# inputsheild_7.net
KiCad netlist of a schematic drawn in EAGLE
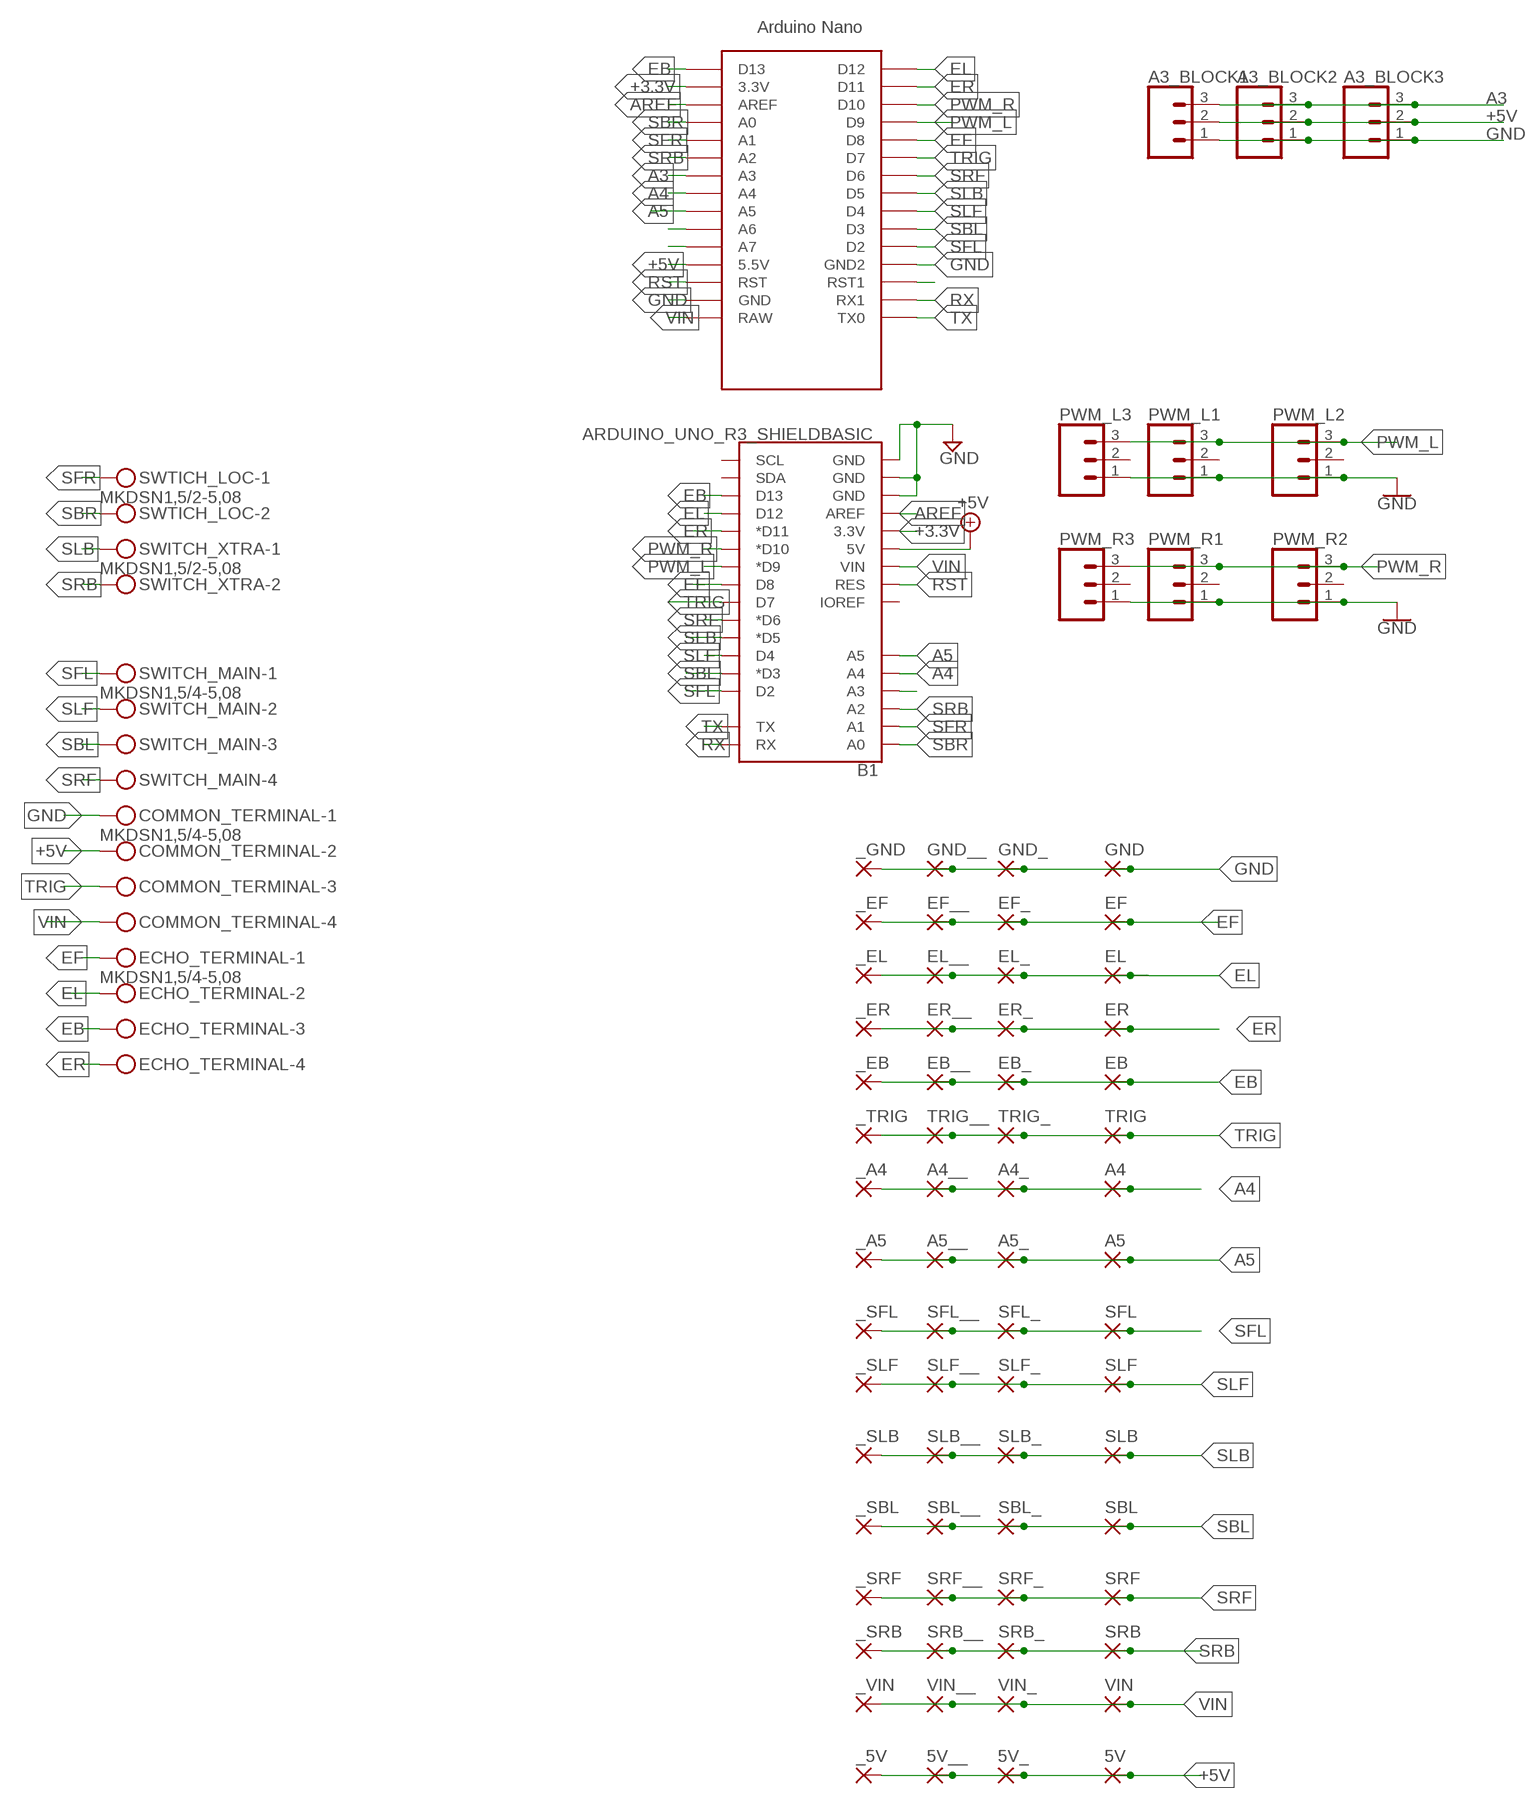
[diagram p0: schematic, sheet 1]

(export (version "E")
  (design (tool "Eeschema 10.0.6"))
  (components
    (comp (ref "5V")
      (value "SMD5")
      (footprint "eagle-import:SMD2,54-5,08")
      (libsource (lib "eagle-import") (part "SMD5"))
    )
    (comp (ref "5V_")
      (value "SMD5")
      (footprint "eagle-import:SMD2,54-5,08")
      (libsource (lib "eagle-import") (part "SMD5"))
    )
    (comp (ref "5V__")
      (value "SMD5")
      (footprint "eagle-import:SMD2,54-5,08")
      (libsource (lib "eagle-import") (part "SMD5"))
    )
    (comp (ref "A3_BLOCK1")
      (value "CONN_03")
      (footprint "eagle-import:1X03")
      (libsource (lib "eagle-import") (part "CONN_03"))
    )
    (comp (ref "A3_BLOCK2")
      (value "CONN_03")
      (footprint "eagle-import:1X03")
      (libsource (lib "eagle-import") (part "CONN_03"))
    )
    (comp (ref "A3_BLOCK3")
      (value "CONN_03")
      (footprint "eagle-import:1X03")
      (libsource (lib "eagle-import") (part "CONN_03"))
    )
    (comp (ref "A4")
      (value "SMD5")
      (footprint "eagle-import:SMD2,54-5,08")
      (libsource (lib "eagle-import") (part "SMD5"))
    )
    (comp (ref "A4_")
      (value "SMD5")
      (footprint "eagle-import:SMD2,54-5,08")
      (libsource (lib "eagle-import") (part "SMD5"))
    )
    (comp (ref "A4__")
      (value "SMD5")
      (footprint "eagle-import:SMD2,54-5,08")
      (libsource (lib "eagle-import") (part "SMD5"))
    )
    (comp (ref "A5")
      (value "SMD5")
      (footprint "eagle-import:SMD2,54-5,08")
      (libsource (lib "eagle-import") (part "SMD5"))
    )
    (comp (ref "A5_")
      (value "SMD5")
      (footprint "eagle-import:SMD2,54-5,08")
      (libsource (lib "eagle-import") (part "SMD5"))
    )
    (comp (ref "A5__")
      (value "SMD5")
      (footprint "eagle-import:SMD2,54-5,08")
      (libsource (lib "eagle-import") (part "SMD5"))
    )
    (comp (ref "B1")
      (value "ARDUINO_UNO_R3_SHIELDBASIC")
      (footprint "eagle-import:UNO_R3_SHIELD")
      (libsource (lib "eagle-import") (part "ARDUINO_UNO_R3_SHIELDBASIC"))
    )
    (comp (ref "COMMON_TERMINAL")
      (value "MKDSN1,5/4-5,08")
      (footprint "eagle-import:MKDSN1,5_4-5,08")
      (libsource (lib "eagle-import") (part "MKDSN1,5/4-5,08"))
    )
    (comp (ref "EB")
      (value "SMD5")
      (footprint "eagle-import:SMD2,54-5,08")
      (libsource (lib "eagle-import") (part "SMD5"))
    )
    (comp (ref "EB_")
      (value "SMD5")
      (footprint "eagle-import:SMD2,54-5,08")
      (libsource (lib "eagle-import") (part "SMD5"))
    )
    (comp (ref "EB__")
      (value "SMD5")
      (footprint "eagle-import:SMD2,54-5,08")
      (libsource (lib "eagle-import") (part "SMD5"))
    )
    (comp (ref "ECHO_TERMINAL")
      (value "MKDSN1,5/4-5,08")
      (footprint "eagle-import:MKDSN1,5_4-5,08")
      (libsource (lib "eagle-import") (part "MKDSN1,5/4-5,08"))
    )
    (comp (ref "EF")
      (value "SMD5")
      (footprint "eagle-import:SMD2,54-5,08")
      (libsource (lib "eagle-import") (part "SMD5"))
    )
    (comp (ref "EF_")
      (value "SMD5")
      (footprint "eagle-import:SMD2,54-5,08")
      (libsource (lib "eagle-import") (part "SMD5"))
    )
    (comp (ref "EF__")
      (value "SMD5")
      (footprint "eagle-import:SMD2,54-5,08")
      (libsource (lib "eagle-import") (part "SMD5"))
    )
    (comp (ref "EL")
      (value "SMD5")
      (footprint "eagle-import:SMD2,54-5,08")
      (libsource (lib "eagle-import") (part "SMD5"))
    )
    (comp (ref "EL_")
      (value "SMD5")
      (footprint "eagle-import:SMD2,54-5,08")
      (libsource (lib "eagle-import") (part "SMD5"))
    )
    (comp (ref "EL__")
      (value "SMD5")
      (footprint "eagle-import:SMD2,54-5,08")
      (libsource (lib "eagle-import") (part "SMD5"))
    )
    (comp (ref "ER")
      (value "SMD5")
      (footprint "eagle-import:SMD2,54-5,08")
      (libsource (lib "eagle-import") (part "SMD5"))
    )
    (comp (ref "ER_")
      (value "SMD5")
      (footprint "eagle-import:SMD2,54-5,08")
      (libsource (lib "eagle-import") (part "SMD5"))
    )
    (comp (ref "ER__")
      (value "SMD5")
      (footprint "eagle-import:SMD2,54-5,08")
      (libsource (lib "eagle-import") (part "SMD5"))
    )
    (comp (ref "GND")
      (value "SMD5")
      (footprint "eagle-import:SMD2,54-5,08")
      (libsource (lib "eagle-import") (part "SMD5"))
    )
    (comp (ref "GND_")
      (value "SMD5")
      (footprint "eagle-import:SMD2,54-5,08")
      (libsource (lib "eagle-import") (part "SMD5"))
    )
    (comp (ref "GND__")
      (value "SMD5")
      (footprint "eagle-import:SMD2,54-5,08")
      (libsource (lib "eagle-import") (part "SMD5"))
    )
    (comp (ref "PWM_L1")
      (value "CONN_03")
      (footprint "eagle-import:1X03")
      (libsource (lib "eagle-import") (part "CONN_03"))
    )
    (comp (ref "PWM_L2")
      (value "CONN_03")
      (footprint "eagle-import:1X03")
      (libsource (lib "eagle-import") (part "CONN_03"))
    )
    (comp (ref "PWM_L3")
      (value "CONN_03")
      (footprint "eagle-import:1X03")
      (libsource (lib "eagle-import") (part "CONN_03"))
    )
    (comp (ref "PWM_R1")
      (value "CONN_03")
      (footprint "eagle-import:1X03")
      (libsource (lib "eagle-import") (part "CONN_03"))
    )
    (comp (ref "PWM_R2")
      (value "CONN_03")
      (footprint "eagle-import:1X03")
      (libsource (lib "eagle-import") (part "CONN_03"))
    )
    (comp (ref "PWM_R3")
      (value "CONN_03")
      (footprint "eagle-import:1X03")
      (libsource (lib "eagle-import") (part "CONN_03"))
    )
    (comp (ref "SBL")
      (value "SMD5")
      (footprint "eagle-import:SMD2,54-5,08")
      (libsource (lib "eagle-import") (part "SMD5"))
    )
    (comp (ref "SBL_")
      (value "SMD5")
      (footprint "eagle-import:SMD2,54-5,08")
      (libsource (lib "eagle-import") (part "SMD5"))
    )
    (comp (ref "SBL__")
      (value "SMD5")
      (footprint "eagle-import:SMD2,54-5,08")
      (libsource (lib "eagle-import") (part "SMD5"))
    )
    (comp (ref "SFL")
      (value "SMD5")
      (footprint "eagle-import:SMD2,54-5,08")
      (libsource (lib "eagle-import") (part "SMD5"))
    )
    (comp (ref "SFL_")
      (value "SMD5")
      (footprint "eagle-import:SMD2,54-5,08")
      (libsource (lib "eagle-import") (part "SMD5"))
    )
    (comp (ref "SFL__")
      (value "SMD5")
      (footprint "eagle-import:SMD2,54-5,08")
      (libsource (lib "eagle-import") (part "SMD5"))
    )
    (comp (ref "SLB")
      (value "SMD5")
      (footprint "eagle-import:SMD2,54-5,08")
      (libsource (lib "eagle-import") (part "SMD5"))
    )
    (comp (ref "SLB_")
      (value "SMD5")
      (footprint "eagle-import:SMD2,54-5,08")
      (libsource (lib "eagle-import") (part "SMD5"))
    )
    (comp (ref "SLB__")
      (value "SMD5")
      (footprint "eagle-import:SMD2,54-5,08")
      (libsource (lib "eagle-import") (part "SMD5"))
    )
    (comp (ref "SLF")
      (value "SMD5")
      (footprint "eagle-import:SMD2,54-5,08")
      (libsource (lib "eagle-import") (part "SMD5"))
    )
    (comp (ref "SLF_")
      (value "SMD5")
      (footprint "eagle-import:SMD2,54-5,08")
      (libsource (lib "eagle-import") (part "SMD5"))
    )
    (comp (ref "SLF__")
      (value "SMD5")
      (footprint "eagle-import:SMD2,54-5,08")
      (libsource (lib "eagle-import") (part "SMD5"))
    )
    (comp (ref "SRB")
      (value "SMD5")
      (footprint "eagle-import:SMD2,54-5,08")
      (libsource (lib "eagle-import") (part "SMD5"))
    )
    (comp (ref "SRB_")
      (value "SMD5")
      (footprint "eagle-import:SMD2,54-5,08")
      (libsource (lib "eagle-import") (part "SMD5"))
    )
    (comp (ref "SRB__")
      (value "SMD5")
      (footprint "eagle-import:SMD2,54-5,08")
      (libsource (lib "eagle-import") (part "SMD5"))
    )
    (comp (ref "SRF")
      (value "SMD5")
      (footprint "eagle-import:SMD2,54-5,08")
      (libsource (lib "eagle-import") (part "SMD5"))
    )
    (comp (ref "SRF_")
      (value "SMD5")
      (footprint "eagle-import:SMD2,54-5,08")
      (libsource (lib "eagle-import") (part "SMD5"))
    )
    (comp (ref "SRF__")
      (value "SMD5")
      (footprint "eagle-import:SMD2,54-5,08")
      (libsource (lib "eagle-import") (part "SMD5"))
    )
    (comp (ref "SWITCH_MAIN")
      (value "MKDSN1,5/4-5,08")
      (footprint "eagle-import:MKDSN1,5_4-5,08")
      (libsource (lib "eagle-import") (part "MKDSN1,5/4-5,08"))
    )
    (comp (ref "SWITCH_XTRA")
      (value "MKDSN1,5/2-5,08")
      (footprint "eagle-import:MKDSN1,5_2-5,08")
      (libsource (lib "eagle-import") (part "MKDSN1,5/2-5,08"))
    )
    (comp (ref "SWTICH_LOC")
      (value "MKDSN1,5/2-5,08")
      (footprint "eagle-import:MKDSN1,5_2-5,08")
      (libsource (lib "eagle-import") (part "MKDSN1,5/2-5,08"))
    )
    (comp (ref "TRIG")
      (value "SMD5")
      (footprint "eagle-import:SMD2,54-5,08")
      (libsource (lib "eagle-import") (part "SMD5"))
    )
    (comp (ref "TRIG_")
      (value "SMD5")
      (footprint "eagle-import:SMD2,54-5,08")
      (libsource (lib "eagle-import") (part "SMD5"))
    )
    (comp (ref "TRIG__")
      (value "SMD5")
      (footprint "eagle-import:SMD2,54-5,08")
      (libsource (lib "eagle-import") (part "SMD5"))
    )
    (comp (ref "U$1")
      (value "NANO")
      (footprint "eagle-import:NANO")
      (libsource (lib "eagle-import") (part "NANO"))
    )
    (comp (ref "VIN")
      (value "SMD5")
      (footprint "eagle-import:SMD2,54-5,08")
      (libsource (lib "eagle-import") (part "SMD5"))
    )
    (comp (ref "VIN_")
      (value "SMD5")
      (footprint "eagle-import:SMD2,54-5,08")
      (libsource (lib "eagle-import") (part "SMD5"))
    )
    (comp (ref "VIN__")
      (value "SMD5")
      (footprint "eagle-import:SMD2,54-5,08")
      (libsource (lib "eagle-import") (part "SMD5"))
    )
    (comp (ref "_5V")
      (value "SMD5")
      (footprint "eagle-import:SMD2,54-5,08")
      (libsource (lib "eagle-import") (part "SMD5"))
    )
    (comp (ref "_A4")
      (value "SMD5")
      (footprint "eagle-import:SMD2,54-5,08")
      (libsource (lib "eagle-import") (part "SMD5"))
    )
    (comp (ref "_A5")
      (value "SMD5")
      (footprint "eagle-import:SMD2,54-5,08")
      (libsource (lib "eagle-import") (part "SMD5"))
    )
    (comp (ref "_EB")
      (value "SMD5")
      (footprint "eagle-import:SMD2,54-5,08")
      (libsource (lib "eagle-import") (part "SMD5"))
    )
    (comp (ref "_EF")
      (value "SMD5")
      (footprint "eagle-import:SMD2,54-5,08")
      (libsource (lib "eagle-import") (part "SMD5"))
    )
    (comp (ref "_EL")
      (value "SMD5")
      (footprint "eagle-import:SMD2,54-5,08")
      (libsource (lib "eagle-import") (part "SMD5"))
    )
    (comp (ref "_ER")
      (value "SMD5")
      (footprint "eagle-import:SMD2,54-5,08")
      (libsource (lib "eagle-import") (part "SMD5"))
    )
    (comp (ref "_GND")
      (value "SMD5")
      (footprint "eagle-import:SMD2,54-5,08")
      (libsource (lib "eagle-import") (part "SMD5"))
    )
    (comp (ref "_SBL")
      (value "SMD5")
      (footprint "eagle-import:SMD2,54-5,08")
      (libsource (lib "eagle-import") (part "SMD5"))
    )
    (comp (ref "_SFL")
      (value "SMD5")
      (footprint "eagle-import:SMD2,54-5,08")
      (libsource (lib "eagle-import") (part "SMD5"))
    )
    (comp (ref "_SLB")
      (value "SMD5")
      (footprint "eagle-import:SMD2,54-5,08")
      (libsource (lib "eagle-import") (part "SMD5"))
    )
    (comp (ref "_SLF")
      (value "SMD5")
      (footprint "eagle-import:SMD2,54-5,08")
      (libsource (lib "eagle-import") (part "SMD5"))
    )
    (comp (ref "_SRB")
      (value "SMD5")
      (footprint "eagle-import:SMD2,54-5,08")
      (libsource (lib "eagle-import") (part "SMD5"))
    )
    (comp (ref "_SRF")
      (value "SMD5")
      (footprint "eagle-import:SMD2,54-5,08")
      (libsource (lib "eagle-import") (part "SMD5"))
    )
    (comp (ref "_TRIG")
      (value "SMD5")
      (footprint "eagle-import:SMD2,54-5,08")
      (libsource (lib "eagle-import") (part "SMD5"))
    )
    (comp (ref "_VIN")
      (value "SMD5")
      (footprint "eagle-import:SMD2,54-5,08")
      (libsource (lib "eagle-import") (part "SMD5"))
    )
  )
  (nets
    (net (code "1") (name "+3.3V") (class "Default")
      (node (ref "B1") (pin "3.3V") (pinfunction "3.3V_3.3V") (pintype "bidirectional"))
      (node (ref "U$1") (pin "3.3V") (pinfunction "3.3V_3.3V") (pintype "bidirectional"))
    )
    (net (code "2") (name "+5V") (class "Default")
      (node (ref "5V") (pin "1") (pinfunction "P_1") (pintype "passive"))
      (node (ref "5V_") (pin "1") (pinfunction "P_1") (pintype "passive"))
      (node (ref "5V__") (pin "1") (pinfunction "P_1") (pintype "passive"))
      (node (ref "A3_BLOCK1") (pin "2") (pinfunction "2_2") (pintype "passive"))
      (node (ref "A3_BLOCK2") (pin "2") (pinfunction "2_2") (pintype "passive"))
      (node (ref "A3_BLOCK3") (pin "2") (pinfunction "2_2") (pintype "passive"))
      (node (ref "B1") (pin "5V") (pinfunction "5V_5V") (pintype "bidirectional"))
      (node (ref "COMMON_TERMINAL") (pin "2") (pinfunction "KL_2") (pintype "passive"))
      (node (ref "U$1") (pin "5V") (pinfunction "5.5V_5V") (pintype "bidirectional"))
      (node (ref "_5V") (pin "1") (pinfunction "P_1") (pintype "passive"))
    )
    (net (code "3") (name "A3") (class "Default")
      (node (ref "A3_BLOCK1") (pin "3") (pinfunction "3_3") (pintype "passive"))
      (node (ref "A3_BLOCK2") (pin "3") (pinfunction "3_3") (pintype "passive"))
      (node (ref "A3_BLOCK3") (pin "3") (pinfunction "3_3") (pintype "passive"))
      (node (ref "U$1") (pin "A3") (pinfunction "A3_A3") (pintype "bidirectional"))
    )
    (net (code "4") (name "A4") (class "Default")
      (node (ref "A4") (pin "1") (pinfunction "P_1") (pintype "passive"))
      (node (ref "A4_") (pin "1") (pinfunction "P_1") (pintype "passive"))
      (node (ref "A4__") (pin "1") (pinfunction "P_1") (pintype "passive"))
      (node (ref "B1") (pin "A4") (pinfunction "A4_A4") (pintype "bidirectional"))
      (node (ref "U$1") (pin "A4") (pinfunction "A4_A4") (pintype "bidirectional"))
      (node (ref "_A4") (pin "1") (pinfunction "P_1") (pintype "passive"))
    )
    (net (code "5") (name "A5") (class "Default")
      (node (ref "A5") (pin "1") (pinfunction "P_1") (pintype "passive"))
      (node (ref "A5_") (pin "1") (pinfunction "P_1") (pintype "passive"))
      (node (ref "A5__") (pin "1") (pinfunction "P_1") (pintype "passive"))
      (node (ref "B1") (pin "A5") (pinfunction "A5_A5") (pintype "bidirectional"))
      (node (ref "U$1") (pin "A5") (pinfunction "A5_A5") (pintype "bidirectional"))
      (node (ref "_A5") (pin "1") (pinfunction "P_1") (pintype "passive"))
    )
    (net (code "6") (name "AREF") (class "Default")
      (node (ref "B1") (pin "AREF") (pinfunction "AREF_AREF") (pintype "bidirectional"))
      (node (ref "U$1") (pin "AREF") (pinfunction "AREF_AREF") (pintype "bidirectional"))
    )
    (net (code "7") (name "EB") (class "Default")
      (node (ref "B1") (pin "D13") (pinfunction "D13_D13") (pintype "bidirectional"))
      (node (ref "EB") (pin "1") (pinfunction "P_1") (pintype "passive"))
      (node (ref "EB_") (pin "1") (pinfunction "P_1") (pintype "passive"))
      (node (ref "EB__") (pin "1") (pinfunction "P_1") (pintype "passive"))
      (node (ref "ECHO_TERMINAL") (pin "3") (pinfunction "KL_3") (pintype "passive"))
      (node (ref "U$1") (pin "D13") (pinfunction "D13_D13") (pintype "bidirectional"))
      (node (ref "_EB") (pin "1") (pinfunction "P_1") (pintype "passive"))
    )
    (net (code "8") (name "EF") (class "Default")
      (node (ref "B1") (pin "D8") (pinfunction "D8_D8") (pintype "bidirectional"))
      (node (ref "ECHO_TERMINAL") (pin "1") (pinfunction "KL_1") (pintype "passive"))
      (node (ref "EF") (pin "1") (pinfunction "P_1") (pintype "passive"))
      (node (ref "EF_") (pin "1") (pinfunction "P_1") (pintype "passive"))
      (node (ref "EF__") (pin "1") (pinfunction "P_1") (pintype "passive"))
      (node (ref "U$1") (pin "D8") (pinfunction "D8_D8") (pintype "bidirectional"))
      (node (ref "_EF") (pin "1") (pinfunction "P_1") (pintype "passive"))
    )
    (net (code "9") (name "EL") (class "Default")
      (node (ref "B1") (pin "D12") (pinfunction "D12_D12") (pintype "bidirectional"))
      (node (ref "ECHO_TERMINAL") (pin "2") (pinfunction "KL_2") (pintype "passive"))
      (node (ref "EL") (pin "1") (pinfunction "P_1") (pintype "passive"))
      (node (ref "EL_") (pin "1") (pinfunction "P_1") (pintype "passive"))
      (node (ref "EL__") (pin "1") (pinfunction "P_1") (pintype "passive"))
      (node (ref "U$1") (pin "D12") (pinfunction "D12_D12") (pintype "bidirectional"))
      (node (ref "_EL") (pin "1") (pinfunction "P_1") (pintype "passive"))
    )
    (net (code "10") (name "ER") (class "Default")
      (node (ref "B1") (pin "D11") (pinfunction "*D11_D11") (pintype "bidirectional"))
      (node (ref "ECHO_TERMINAL") (pin "4") (pinfunction "KL_4") (pintype "passive"))
      (node (ref "ER") (pin "1") (pinfunction "P_1") (pintype "passive"))
      (node (ref "ER_") (pin "1") (pinfunction "P_1") (pintype "passive"))
      (node (ref "ER__") (pin "1") (pinfunction "P_1") (pintype "passive"))
      (node (ref "U$1") (pin "D11") (pinfunction "D11_D11") (pintype "bidirectional"))
      (node (ref "_ER") (pin "1") (pinfunction "P_1") (pintype "passive"))
    )
    (net (code "11") (name "GND") (class "Default")
      (node (ref "A3_BLOCK1") (pin "1") (pinfunction "1_1") (pintype "passive"))
      (node (ref "A3_BLOCK2") (pin "1") (pinfunction "1_1") (pintype "passive"))
      (node (ref "A3_BLOCK3") (pin "1") (pinfunction "1_1") (pintype "passive"))
      (node (ref "B1") (pin "GND@0") (pinfunction "GND_GND@0") (pintype "bidirectional"))
      (node (ref "B1") (pin "GND@1") (pinfunction "GND_GND@1") (pintype "bidirectional"))
      (node (ref "B1") (pin "GND@2") (pinfunction "GND_GND@2") (pintype "bidirectional"))
      (node (ref "COMMON_TERMINAL") (pin "1") (pinfunction "KL_1") (pintype "passive"))
      (node (ref "GND") (pin "1") (pinfunction "P_1") (pintype "passive"))
      (node (ref "GND_") (pin "1") (pinfunction "P_1") (pintype "passive"))
      (node (ref "GND__") (pin "1") (pinfunction "P_1") (pintype "passive"))
      (node (ref "PWM_L1") (pin "1") (pinfunction "1_1") (pintype "passive"))
      (node (ref "PWM_L2") (pin "1") (pinfunction "1_1") (pintype "passive"))
      (node (ref "PWM_L3") (pin "1") (pinfunction "1_1") (pintype "passive"))
      (node (ref "PWM_R1") (pin "1") (pinfunction "1_1") (pintype "passive"))
      (node (ref "PWM_R2") (pin "1") (pinfunction "1_1") (pintype "passive"))
      (node (ref "PWM_R3") (pin "1") (pinfunction "1_1") (pintype "passive"))
      (node (ref "U$1") (pin "GND") (pinfunction "GND_GND") (pintype "bidirectional"))
      (node (ref "U$1") (pin "GND1") (pinfunction "GND2_GND1") (pintype "bidirectional"))
      (node (ref "_GND") (pin "1") (pinfunction "P_1") (pintype "passive"))
    )
    (net (code "12") (name "PWM_L") (class "Default")
      (node (ref "B1") (pin "D9") (pinfunction "*D9_D9") (pintype "bidirectional"))
      (node (ref "PWM_L1") (pin "3") (pinfunction "3_3") (pintype "passive"))
      (node (ref "PWM_L2") (pin "3") (pinfunction "3_3") (pintype "passive"))
      (node (ref "PWM_L3") (pin "3") (pinfunction "3_3") (pintype "passive"))
      (node (ref "U$1") (pin "D9") (pinfunction "D9_D9") (pintype "bidirectional"))
    )
    (net (code "13") (name "PWM_R") (class "Default")
      (node (ref "B1") (pin "D10") (pinfunction "*D10_D10") (pintype "bidirectional"))
      (node (ref "PWM_R1") (pin "3") (pinfunction "3_3") (pintype "passive"))
      (node (ref "PWM_R2") (pin "3") (pinfunction "3_3") (pintype "passive"))
      (node (ref "PWM_R3") (pin "3") (pinfunction "3_3") (pintype "passive"))
      (node (ref "U$1") (pin "D10") (pinfunction "D10_D10") (pintype "bidirectional"))
    )
    (net (code "14") (name "RST") (class "Default")
      (node (ref "B1") (pin "RES") (pinfunction "RES_RES") (pintype "bidirectional"))
      (node (ref "U$1") (pin "RST") (pinfunction "RST_RST") (pintype "bidirectional"))
    )
    (net (code "15") (name "RX") (class "Default")
      (node (ref "B1") (pin "RX") (pinfunction "RX_RX") (pintype "bidirectional"))
      (node (ref "U$1") (pin "RX1") (pinfunction "RX1_RX1") (pintype "bidirectional"))
    )
    (net (code "16") (name "SBL") (class "Default")
      (node (ref "B1") (pin "D3") (pinfunction "*D3_D3") (pintype "bidirectional"))
      (node (ref "SBL") (pin "1") (pinfunction "P_1") (pintype "passive"))
      (node (ref "SBL_") (pin "1") (pinfunction "P_1") (pintype "passive"))
      (node (ref "SBL__") (pin "1") (pinfunction "P_1") (pintype "passive"))
      (node (ref "SWITCH_MAIN") (pin "3") (pinfunction "KL_3") (pintype "passive"))
      (node (ref "U$1") (pin "D3") (pinfunction "D3_D3") (pintype "bidirectional"))
      (node (ref "_SBL") (pin "1") (pinfunction "P_1") (pintype "passive"))
    )
    (net (code "17") (name "SBR") (class "Default")
      (node (ref "B1") (pin "A0") (pinfunction "A0_A0") (pintype "bidirectional"))
      (node (ref "SWTICH_LOC") (pin "2") (pinfunction "KL_2") (pintype "passive"))
      (node (ref "U$1") (pin "A0") (pinfunction "A0_A0") (pintype "bidirectional"))
    )
    (net (code "18") (name "SFL") (class "Default")
      (node (ref "B1") (pin "D2") (pinfunction "D2_D2") (pintype "bidirectional"))
      (node (ref "SFL") (pin "1") (pinfunction "P_1") (pintype "passive"))
      (node (ref "SFL_") (pin "1") (pinfunction "P_1") (pintype "passive"))
      (node (ref "SFL__") (pin "1") (pinfunction "P_1") (pintype "passive"))
      (node (ref "SWITCH_MAIN") (pin "1") (pinfunction "KL_1") (pintype "passive"))
      (node (ref "U$1") (pin "D2") (pinfunction "D2_D2") (pintype "bidirectional"))
      (node (ref "_SFL") (pin "1") (pinfunction "P_1") (pintype "passive"))
    )
    (net (code "19") (name "SFR") (class "Default")
      (node (ref "B1") (pin "A1") (pinfunction "A1_A1") (pintype "bidirectional"))
      (node (ref "SWTICH_LOC") (pin "1") (pinfunction "KL_1") (pintype "passive"))
      (node (ref "U$1") (pin "A1") (pinfunction "A1_A1") (pintype "bidirectional"))
    )
    (net (code "20") (name "SLB") (class "Default")
      (node (ref "B1") (pin "D5") (pinfunction "*D5_D5") (pintype "bidirectional"))
      (node (ref "SLB") (pin "1") (pinfunction "P_1") (pintype "passive"))
      (node (ref "SLB_") (pin "1") (pinfunction "P_1") (pintype "passive"))
      (node (ref "SLB__") (pin "1") (pinfunction "P_1") (pintype "passive"))
      (node (ref "SWITCH_XTRA") (pin "1") (pinfunction "KL_1") (pintype "passive"))
      (node (ref "U$1") (pin "D5") (pinfunction "D5_D5") (pintype "bidirectional"))
      (node (ref "_SLB") (pin "1") (pinfunction "P_1") (pintype "passive"))
    )
    (net (code "21") (name "SLF") (class "Default")
      (node (ref "B1") (pin "D4") (pinfunction "D4_D4") (pintype "bidirectional"))
      (node (ref "SLF") (pin "1") (pinfunction "P_1") (pintype "passive"))
      (node (ref "SLF_") (pin "1") (pinfunction "P_1") (pintype "passive"))
      (node (ref "SLF__") (pin "1") (pinfunction "P_1") (pintype "passive"))
      (node (ref "SWITCH_MAIN") (pin "2") (pinfunction "KL_2") (pintype "passive"))
      (node (ref "U$1") (pin "D4") (pinfunction "D4_D4") (pintype "bidirectional"))
      (node (ref "_SLF") (pin "1") (pinfunction "P_1") (pintype "passive"))
    )
    (net (code "22") (name "SRB") (class "Default")
      (node (ref "B1") (pin "A2") (pinfunction "A2_A2") (pintype "bidirectional"))
      (node (ref "SRB") (pin "1") (pinfunction "P_1") (pintype "passive"))
      (node (ref "SRB_") (pin "1") (pinfunction "P_1") (pintype "passive"))
      (node (ref "SRB__") (pin "1") (pinfunction "P_1") (pintype "passive"))
      (node (ref "SWITCH_XTRA") (pin "2") (pinfunction "KL_2") (pintype "passive"))
      (node (ref "U$1") (pin "A2") (pinfunction "A2_A2") (pintype "bidirectional"))
      (node (ref "_SRB") (pin "1") (pinfunction "P_1") (pintype "passive"))
    )
    (net (code "23") (name "SRF") (class "Default")
      (node (ref "B1") (pin "D6") (pinfunction "*D6_D6") (pintype "bidirectional"))
      (node (ref "SRF") (pin "1") (pinfunction "P_1") (pintype "passive"))
      (node (ref "SRF_") (pin "1") (pinfunction "P_1") (pintype "passive"))
      (node (ref "SRF__") (pin "1") (pinfunction "P_1") (pintype "passive"))
      (node (ref "SWITCH_MAIN") (pin "4") (pinfunction "KL_4") (pintype "passive"))
      (node (ref "U$1") (pin "D6") (pinfunction "D6_D6") (pintype "bidirectional"))
      (node (ref "_SRF") (pin "1") (pinfunction "P_1") (pintype "passive"))
    )
    (net (code "24") (name "TRIG") (class "Default")
      (node (ref "B1") (pin "D7") (pinfunction "D7_D7") (pintype "bidirectional"))
      (node (ref "COMMON_TERMINAL") (pin "3") (pinfunction "KL_3") (pintype "passive"))
      (node (ref "TRIG") (pin "1") (pinfunction "P_1") (pintype "passive"))
      (node (ref "TRIG_") (pin "1") (pinfunction "P_1") (pintype "passive"))
      (node (ref "TRIG__") (pin "1") (pinfunction "P_1") (pintype "passive"))
      (node (ref "U$1") (pin "D7") (pinfunction "D7_D7") (pintype "bidirectional"))
      (node (ref "_TRIG") (pin "1") (pinfunction "P_1") (pintype "passive"))
    )
    (net (code "25") (name "TX") (class "Default")
      (node (ref "B1") (pin "TX") (pinfunction "TX_TX") (pintype "bidirectional"))
      (node (ref "U$1") (pin "TX0") (pinfunction "TX0_TX0") (pintype "bidirectional"))
    )
    (net (code "26") (name "VIN") (class "Default")
      (node (ref "B1") (pin "VIN") (pinfunction "VIN_VIN") (pintype "bidirectional"))
      (node (ref "COMMON_TERMINAL") (pin "4") (pinfunction "KL_4") (pintype "passive"))
      (node (ref "U$1") (pin "RAW") (pinfunction "RAW_RAW") (pintype "bidirectional"))
      (node (ref "VIN") (pin "1") (pinfunction "P_1") (pintype "passive"))
      (node (ref "VIN_") (pin "1") (pinfunction "P_1") (pintype "passive"))
      (node (ref "VIN__") (pin "1") (pinfunction "P_1") (pintype "passive"))
      (node (ref "_VIN") (pin "1") (pinfunction "P_1") (pintype "passive"))
    )
    (net (code "27") (name "unconnected-(B1-PadA3)") (class "Default")
      (node (ref "B1") (pin "A3") (pinfunction "A3_A3") (pintype "bidirectional"))
    )
    (net (code "28") (name "unconnected-(B1-PadIOREF)") (class "Default")
      (node (ref "B1") (pin "IOREF") (pinfunction "IOREF_IOREF") (pintype "bidirectional"))
    )
    (net (code "29") (name "unconnected-(B1-PadSCL)") (class "Default")
      (node (ref "B1") (pin "SCL") (pinfunction "SCL_SCL") (pintype "bidirectional"))
    )
    (net (code "30") (name "unconnected-(B1-PadSDA)") (class "Default")
      (node (ref "B1") (pin "SDA") (pinfunction "SDA_SDA") (pintype "bidirectional"))
    )
    (net (code "31") (name "unconnected-(PWM_L1-Pad2)") (class "Default")
      (node (ref "PWM_L1") (pin "2") (pinfunction "2_2") (pintype "passive"))
    )
    (net (code "32") (name "unconnected-(PWM_L2-Pad2)") (class "Default")
      (node (ref "PWM_L2") (pin "2") (pinfunction "2_2") (pintype "passive"))
    )
    (net (code "33") (name "unconnected-(PWM_L3-Pad2)") (class "Default")
      (node (ref "PWM_L3") (pin "2") (pinfunction "2_2") (pintype "passive"))
    )
    (net (code "34") (name "unconnected-(PWM_R1-Pad2)") (class "Default")
      (node (ref "PWM_R1") (pin "2") (pinfunction "2_2") (pintype "passive"))
    )
    (net (code "35") (name "unconnected-(PWM_R2-Pad2)") (class "Default")
      (node (ref "PWM_R2") (pin "2") (pinfunction "2_2") (pintype "passive"))
    )
    (net (code "36") (name "unconnected-(PWM_R3-Pad2)") (class "Default")
      (node (ref "PWM_R3") (pin "2") (pinfunction "2_2") (pintype "passive"))
    )
    (net (code "37") (name "unconnected-(U$1-PadA6)") (class "Default")
      (node (ref "U$1") (pin "A6") (pinfunction "A6_A6") (pintype "bidirectional"))
    )
    (net (code "38") (name "unconnected-(U$1-PadA7)") (class "Default")
      (node (ref "U$1") (pin "A7") (pinfunction "A7_A7") (pintype "bidirectional"))
    )
    (net (code "39") (name "unconnected-(U$1-PadICSP1)") (class "Default")
      (node (ref "U$1") (pin "ICSP1") (pinfunction "ICSP1_ICSP1") (pintype "bidirectional"))
    )
    (net (code "40") (name "unconnected-(U$1-PadICSP2)") (class "Default")
      (node (ref "U$1") (pin "ICSP2") (pinfunction "ICSP2_ICSP2") (pintype "bidirectional"))
    )
    (net (code "41") (name "unconnected-(U$1-PadICSP3)") (class "Default")
      (node (ref "U$1") (pin "ICSP3") (pinfunction "ICSP3_ICSP3") (pintype "bidirectional"))
    )
    (net (code "42") (name "unconnected-(U$1-PadICSP4)") (class "Default")
      (node (ref "U$1") (pin "ICSP4") (pinfunction "ICSP4_ICSP4") (pintype "bidirectional"))
    )
    (net (code "43") (name "unconnected-(U$1-PadICSP5)") (class "Default")
      (node (ref "U$1") (pin "ICSP5") (pinfunction "ICSP5_ICSP5") (pintype "bidirectional"))
    )
    (net (code "44") (name "unconnected-(U$1-PadICSP6)") (class "Default")
      (node (ref "U$1") (pin "ICSP6") (pinfunction "ICSP6_ICSP6") (pintype "bidirectional"))
    )
    (net (code "45") (name "unconnected-(U$1-PadRST1)") (class "Default")
      (node (ref "U$1") (pin "RST1") (pinfunction "RST1_RST1") (pintype "bidirectional"))
    )
  )
)
